# ModPowerBlock.net
KiCad netlist of a schematic drawn in Altium Designer
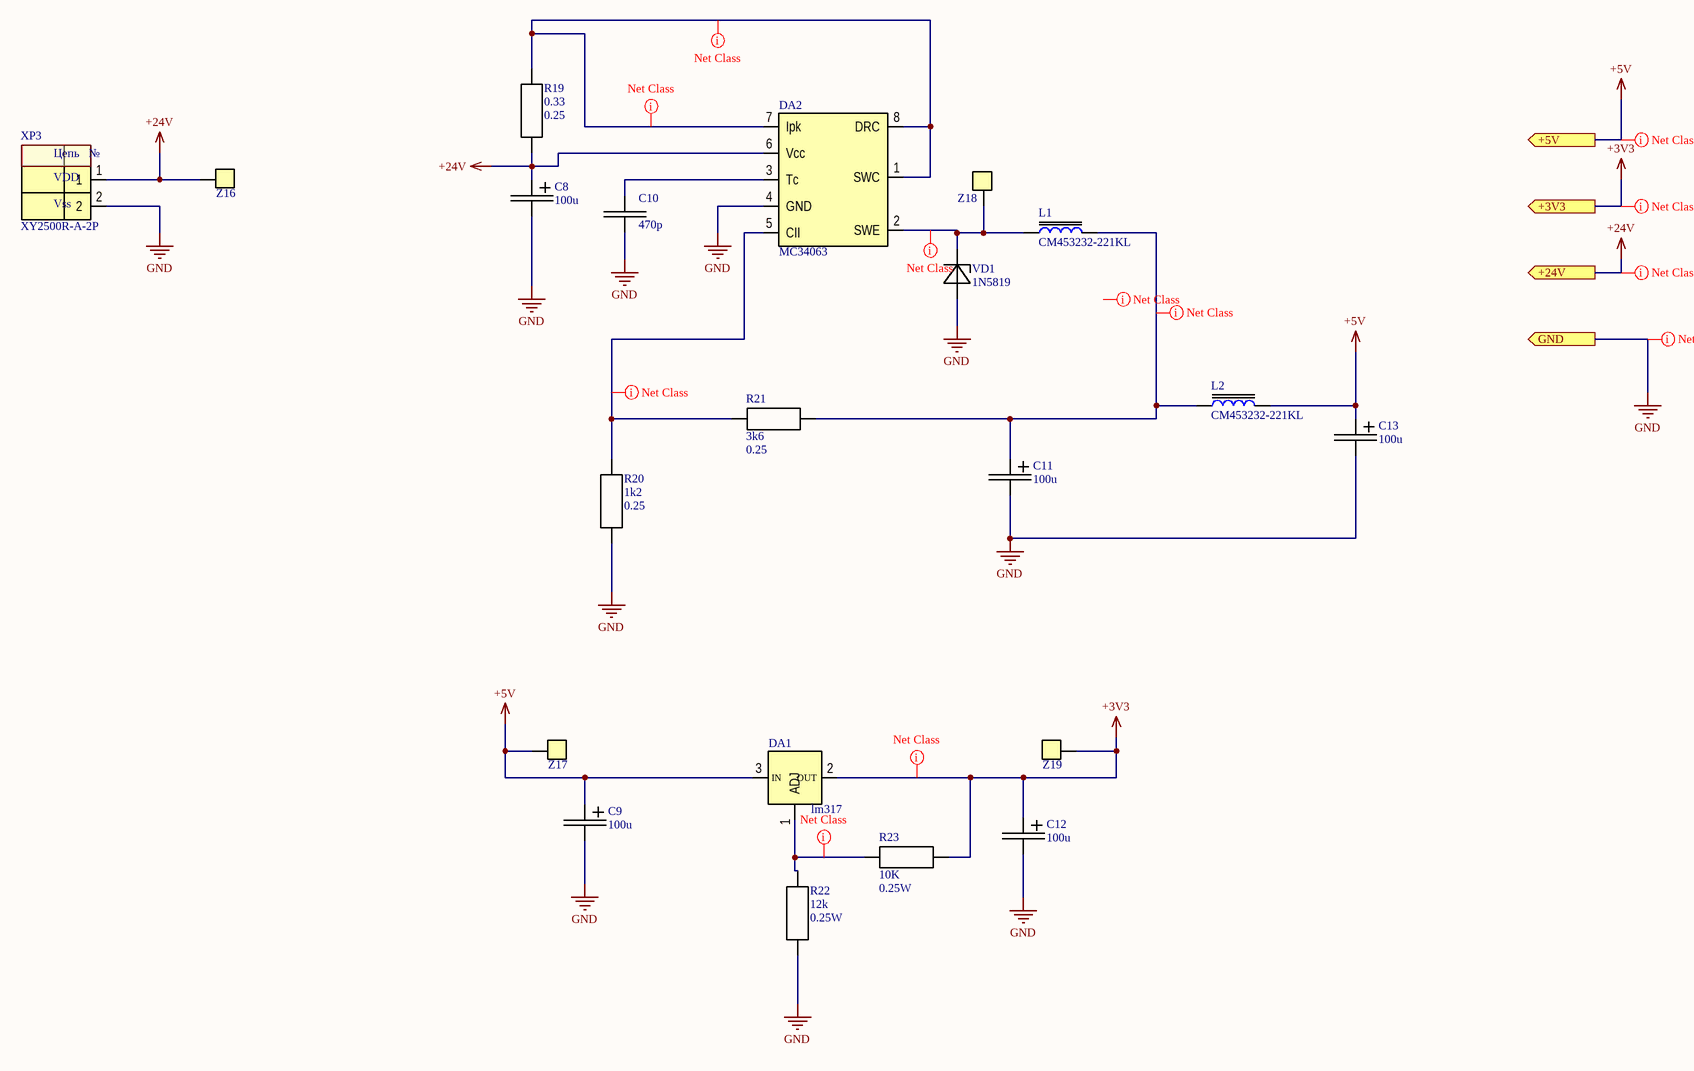
[diagram p0: ModPowerBlock.SchDoc]

(export (version "E")
  (design (tool "Eeschema 10.0.6"))
  (components
    (comp (ref "C8")
      (value "100u")
      (footprint "CAPAE120103X105MTypeG")
      (fields (field (name "MANUFACTURER") "Samwha") (field (name "POWER") "50V"))
      (libsource (lib "SchlibUGO") (part "Capasitor Electrolit"))
    )
    (comp (ref "C9")
      (value "100u")
      (footprint "CAPAE120103X105MTypeG")
      (fields (field (name "MANUFACTURER") "Samwha") (field (name "POWER") "50V"))
      (libsource (lib "SchlibUGO") (part "Capasitor Electrolit"))
    )
    (comp (ref "C10")
      (value "470p")
      (footprint "CAP1206")
      (fields
        (field (name "VOLTAGE") "50V")
        (field (name "PART NUMBER") "1206471X7R")
        (field (name "MANUFACTURER") "FAITHFULL LINK")
      )
      (libsource (lib "SchlibUGO") (part "Capasitor"))
    )
    (comp (ref "C11")
      (value "100u")
      (footprint "CAPAE120103X105MTypeG")
      (fields (field (name "MANUFACTURER") "Samwha") (field (name "POWER") "50V"))
      (libsource (lib "SchlibUGO") (part "Capasitor Electrolit"))
    )
    (comp (ref "C12")
      (value "100u")
      (footprint "CAPAE120103X105MTypeG")
      (fields (field (name "MANUFACTURER") "Samwha") (field (name "POWER") "50V"))
      (libsource (lib "SchlibUGO") (part "Capasitor Electrolit"))
    )
    (comp (ref "C13")
      (value "100u")
      (footprint "CAPAE120103X105MTypeG")
      (fields (field (name "MANUFACTURER") "Samwha") (field (name "POWER") "50V"))
      (libsource (lib "SchlibUGO") (part "Capasitor Electrolit"))
    )
    (comp (ref "DA1")
      (value "lm317")
      (footprint "SOD-223")
      (fields (field (name "MANUFACTURER") "Texas Instruments") (field (name "PART NUMBER") "LM317AEMP/NOPB"))
      (libsource (lib "SchlibUGO") (part "lm317"))
    )
    (comp (ref "DA2")
      (value "MC34063")
      (footprint "SO-8")
      (fields (field (name "PART NUMBER") "MC34063ADR") (field (name "MANUFACTURER") "ON Semiconductor"))
      (libsource (lib "SchlibUGO") (part "MC34063"))
    )
    (comp (ref "L1")
      (value "CM453232-221KL")
      (footprint "453232")
      (fields (field (name "MANUFACTURER") "Bourns"))
      (libsource (lib "SchlibUGO") (part "CM453232-221KL"))
    )
    (comp (ref "L2")
      (value "CM453232-221KL")
      (footprint "453232")
      (fields (field (name "MANUFACTURER") "Bourns"))
      (libsource (lib "SchlibUGO") (part "CM453232-221KL"))
    )
    (comp (ref "R19")
      (value "0.33")
      (footprint "1206")
      (fields
        (field (name "MANUFACTURER") "Royal Ohm")
        (field (name "PART NUMBER") "1206R033")
        (field (name "POWER") "0.25")
      )
      (libsource (lib "SchlibUGO") (part "Resistor"))
    )
    (comp (ref "R20")
      (value "1k2")
      (footprint "1206")
      (fields
        (field (name "MANUFACTURER") "Royal Ohm")
        (field (name "PART NUMBER") "1206R122")
        (field (name "POWER") "0.25")
      )
      (libsource (lib "SchlibUGO") (part "Resistor"))
    )
    (comp (ref "R21")
      (value "3k6")
      (footprint "1206")
      (fields
        (field (name "MANUFACTURER") "Royal Ohm")
        (field (name "PART NUMBER") "1206R362")
        (field (name "POWER") "0.25")
      )
      (libsource (lib "SchlibUGO") (part "Resistor"))
    )
    (comp (ref "R22")
      (value "12k")
      (footprint "1206")
      (fields
        (field (name "MANUFACTURER") "YAGEO")
        (field (name "PART NUMBER") "RC1206FR-0710KL")
        (field (name "POWER") "0.25W")
      )
      (libsource (lib "SchlibUGO") (part "Resistor"))
    )
    (comp (ref "R23")
      (value "10K")
      (footprint "1206")
      (fields
        (field (name "MANUFACTURER") "YAGEO")
        (field (name "PART NUMBER") "RC1206FR-0710KL")
        (field (name "POWER") "0.25W")
        (field (name "Comment") "10k")
      )
      (libsource (lib "SchlibUGO") (part "Resistor"))
    )
    (comp (ref "VD1")
      (value "1N5819")
      (footprint "SOD-123")
      (fields (field (name "MANUFACTURER") "GALAXY") (field (name "POWER") "1A"))
      (libsource (lib "SchlibUGO") (part "1N5819"))
    )
    (comp (ref "XP3")
      (value "XY2500R-A-2P")
      (footprint "KLS2-EDR-500-2P")
      (libsource (lib "SchlibUGO") (part "Connector_Power"))
    )
    (comp (ref "Z16")
      (value "test Point")
      (footprint "test Point")
      (libsource (lib "") (part "test Point_1"))
    )
    (comp (ref "Z17")
      (value "test Point")
      (footprint "test Point")
      (libsource (lib "") (part "test Point_1"))
    )
    (comp (ref "Z18")
      (value "test Point")
      (footprint "test Point")
      (libsource (lib "SchlibUGO") (part "test Point"))
    )
    (comp (ref "Z19")
      (value "test Point")
      (footprint "test Point")
      (libsource (lib "") (part "test Point_2"))
    )
  )
  (nets
    (net (code "1") (name "+3V3") (class "Default")
      (node (ref "C12") (pin "1") (pinfunction "1_1") (pintype "passive"))
      (node (ref "DA1") (pin "2") (pinfunction "OUT_2") (pintype "passive"))
      (node (ref "R23") (pin "2") (pinfunction "2_2") (pintype "passive"))
      (node (ref "Z19") (pin "1") (pinfunction "1_1") (pintype "passive"))
    )
    (net (code "2") (name "+5V") (class "Default")
      (node (ref "C13") (pin "1") (pinfunction "1_1") (pintype "passive"))
      (node (ref "C9") (pin "1") (pinfunction "1_1") (pintype "passive"))
      (node (ref "DA1") (pin "3") (pinfunction "IN_3") (pintype "passive"))
      (node (ref "L2") (pin "2") (pinfunction "2_2") (pintype "passive"))
      (node (ref "Z17") (pin "1") (pinfunction "1_1") (pintype "passive"))
    )
    (net (code "3") (name "+24V") (class "Default")
      (node (ref "C8") (pin "1") (pinfunction "1_1") (pintype "passive"))
      (node (ref "DA2") (pin "6") (pinfunction "Vcc_6") (pintype "passive"))
      (node (ref "R19") (pin "1") (pinfunction "1_1") (pintype "passive"))
      (node (ref "XP3") (pin "1") (pinfunction "1_1") (pintype "passive"))
      (node (ref "Z16") (pin "1") (pinfunction "1_1") (pintype "passive"))
    )
    (net (code "4") (name "GND") (class "Default")
      (node (ref "C10") (pin "2") (pinfunction "2_2") (pintype "passive"))
      (node (ref "C11") (pin "2") (pinfunction "2_2") (pintype "passive"))
      (node (ref "C12") (pin "2") (pinfunction "2_2") (pintype "passive"))
      (node (ref "C13") (pin "2") (pinfunction "2_2") (pintype "passive"))
      (node (ref "C8") (pin "2") (pinfunction "2_2") (pintype "passive"))
      (node (ref "C9") (pin "2") (pinfunction "2_2") (pintype "passive"))
      (node (ref "DA2") (pin "4") (pinfunction "GND_4") (pintype "passive"))
      (node (ref "R20") (pin "2") (pinfunction "2_2") (pintype "passive"))
      (node (ref "R22") (pin "2") (pinfunction "2_2") (pintype "passive"))
      (node (ref "VD1") (pin "1") (pinfunction "1_1") (pintype "passive"))
      (node (ref "XP3") (pin "2") (pinfunction "2_2") (pintype "passive"))
    )
    (net (code "5") (name "Net-(C11-Pad1)") (class "Default")
      (node (ref "C11") (pin "1") (pinfunction "1_1") (pintype "passive"))
      (node (ref "L1") (pin "2") (pinfunction "2_2") (pintype "passive"))
      (node (ref "L2") (pin "1") (pinfunction "1_1") (pintype "passive"))
      (node (ref "R21") (pin "2") (pinfunction "2_2") (pintype "passive"))
    )
    (net (code "6") (name "Net-(DA1-ADJ)") (class "Default")
      (node (ref "DA1") (pin "1") (pinfunction "ADJ_1") (pintype "passive"))
      (node (ref "R22") (pin "1") (pinfunction "1_1") (pintype "passive"))
      (node (ref "R23") (pin "1") (pinfunction "1_1") (pintype "passive"))
    )
    (net (code "7") (name "Net-(DA2-CII)") (class "Default")
      (node (ref "DA2") (pin "5") (pinfunction "CII_5") (pintype "passive"))
      (node (ref "R20") (pin "1") (pinfunction "1_1") (pintype "passive"))
      (node (ref "R21") (pin "1") (pinfunction "1_1") (pintype "passive"))
    )
    (net (code "8") (name "Net-(DA2-DRC)") (class "Default")
      (node (ref "DA2") (pin "1") (pinfunction "SWC_1") (pintype "passive"))
      (node (ref "DA2") (pin "7") (pinfunction "Ipk_7") (pintype "passive"))
      (node (ref "DA2") (pin "8") (pinfunction "DRC_8") (pintype "passive"))
      (node (ref "R19") (pin "2") (pinfunction "2_2") (pintype "passive"))
    )
    (net (code "9") (name "Net-(DA2-SWE)") (class "Default")
      (node (ref "DA2") (pin "2") (pinfunction "SWE_2") (pintype "passive"))
      (node (ref "L1") (pin "1") (pinfunction "1_1") (pintype "passive"))
      (node (ref "VD1") (pin "2") (pinfunction "2_2") (pintype "passive"))
      (node (ref "Z18") (pin "1") (pinfunction "1_1") (pintype "passive"))
    )
    (net (code "10") (name "Net-(DA2-Tc)") (class "Default")
      (node (ref "C10") (pin "1") (pinfunction "1_1") (pintype "passive"))
      (node (ref "DA2") (pin "3") (pinfunction "Tc_3") (pintype "passive"))
    )
  )
)
